# STEP_DOWN.net
KiCad netlist of a schematic drawn in Altium Designer
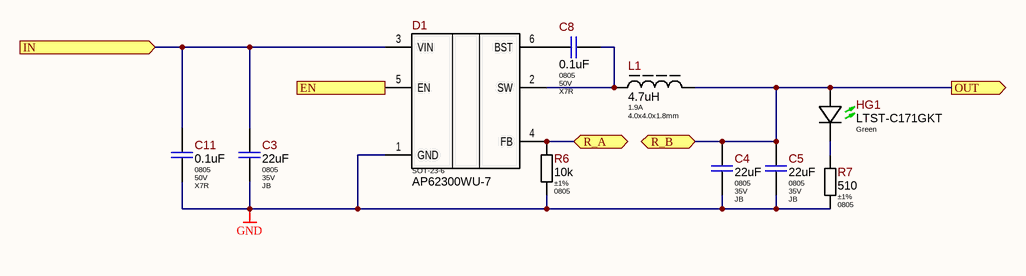
[diagram p0: STEP_DOWN.SchDoc]

(export (version "E")
  (design (tool "Eeschema 10.0.6"))
  (components
    (comp (ref "C3")
      (value "22uF")
      (footprint "CAP-0805(2012)X125T20")
      (description "22uF 35V JB ±20% 0805 Ceramic Capacitor RoHS")
      (fields
        (field (name "PACKAGE") "0805")
        (field (name "VOLTAGE") "35V")
        (field (name "DIELECTRIC TYPE") "JB")
        (field (name "PART NUMBER") "C2012JB1V226M125AC")
        (field (name "MANUFACTURER") "TDK Corporation")
      )
      (libsource (lib "capacitors") (part "C2012JB1V226M125AC"))
    )
    (comp (ref "C4")
      (value "22uF")
      (footprint "CAP-0805(2012)X125T20")
      (description "22uF 35V JB ±20% 0805 Ceramic Capacitor RoHS")
      (fields
        (field (name "PACKAGE") "0805")
        (field (name "VOLTAGE") "35V")
        (field (name "DIELECTRIC TYPE") "JB")
        (field (name "PART NUMBER") "C2012JB1V226M125AC")
        (field (name "MANUFACTURER") "TDK Corporation")
      )
      (libsource (lib "capacitors") (part "C2012JB1V226M125AC"))
    )
    (comp (ref "C5")
      (value "22uF")
      (footprint "CAP-0805(2012)X125T20")
      (description "22uF 35V JB ±20% 0805 Ceramic Capacitor RoHS")
      (fields
        (field (name "PACKAGE") "0805")
        (field (name "VOLTAGE") "35V")
        (field (name "DIELECTRIC TYPE") "JB")
        (field (name "PART NUMBER") "C2012JB1V226M125AC")
        (field (name "MANUFACTURER") "TDK Corporation")
      )
      (libsource (lib "capacitors") (part "C2012JB1V226M125AC"))
    )
    (comp (ref "C8")
      (value "0.1uF")
      (footprint "CAP-0805(2012)X85T10")
      (description "100nF 50V X7R ±10% 0805 Ceramic Capacitor RoHS")
      (fields
        (field (name "PACKAGE") "0805")
        (field (name "VOLTAGE") "50V")
        (field (name "DIELECTRIC TYPE") "X7R")
        (field (name "PART NUMBER") "CL21B104KBCNNNC")
        (field (name "MANUFACTURER") "Samsung Electro-Mechanics")
      )
      (libsource (lib "capacitors") (part "CL21B104KBCNNNC"))
    )
    (comp (ref "C11")
      (value "0.1uF")
      (footprint "CAP-0805(2012)X85T10")
      (description "100nF 50V X7R ±10% 0805 Ceramic Capacitor RoHS")
      (fields
        (field (name "PACKAGE") "0805")
        (field (name "VOLTAGE") "50V")
        (field (name "DIELECTRIC TYPE") "X7R")
        (field (name "PART NUMBER") "CL21B104KBCNNNC")
        (field (name "MANUFACTURER") "Samsung Electro-Mechanics")
      )
      (libsource (lib "capacitors") (part "CL21B104KBCNNNC"))
    )
    (comp (ref "D1")
      (value "AP62300WU-7")
      (footprint "SOT-23-6")
      (description "4.35V to 18V, 2A, High Efficiency Synchronous Step Down Converter, 500kHz, SOT-23-6")
      (fields
        (field (name "MANUFACTURER") "Diodes Incorporated")
        (field (name "PACKAGE") "SOT-23-6")
        (field (name "PART NUMBER") "AP62300WU-7")
      )
      (libsource (lib "CAMLIB") (part "AP62300WU-7"))
    )
    (comp (ref "HG1")
      (value "LTST-C171GKT")
      (footprint "LTST-C171GKT")
      (description "Low Power LED, Green 565nm, Clear, SMD 0805, Vf 2.1V - 2.6V, 5 ~ 12mcd @ 20 mA, 130°")
      (fields
        (field (name "PART NUMBER") "LTST-C171GKT")
        (field (name "COLOR") "Green")
        (field (name "MANUFACTURER") "Lite-On Optoelectronics")
      )
      (libsource (lib "opto") (part "LTST-C171GKT"))
    )
    (comp (ref "L1")
      (value "4.7uH")
      (footprint "SRN4018-Series_1.8mm")
      (description "4.7uH Semi-Shielded Wirewound Inductor 1.9A 84mOhm Max")
      (fields
        (field (name "CURRENT") "1.9A")
        (field (name "PACKAGE") "4.0x4.0x1.8mm")
        (field (name "PART NUMBER") "SRN4018-4R7M")
        (field (name "TOLERANCE") "±20%")
      )
      (libsource (lib "inductors") (part "SRN4018-4R7M"))
    )
    (comp (ref "R6")
      (value "10k")
      (footprint "R_ANY_CHIP_0805_MED")
      (description "10 kOhms ±1%, 1/8W 0805 Thick Film Resistor")
      (fields
        (field (name "TOLERANCE") "±1%")
        (field (name "PACKAGE") "0805")
        (field (name "PART NUMBER") "RC0805FR-0710K2L")
        (field (name "MANUFACTURER") "Yageo")
      )
      (libsource (lib "resistors") (part "RC0805FR-0710K2L"))
    )
    (comp (ref "R7")
      (value "510")
      (footprint "R_ANY_CHIP_0805_MED")
      (description "510 Ohms ±1%, 1/2W 0805 High Power Thick Film Resistor")
      (fields
        (field (name "TOLERANCE") "±1%")
        (field (name "PACKAGE") "0805")
        (field (name "PART NUMBER") "ERJ-P06F5100V")
        (field (name "MANUFACTURER") "Panasonic")
      )
      (libsource (lib "resistors") (part "ERJ-P06F5100V"))
    )
  )
  (nets
    (net (code "1") (name "/EN") (class "Default")
      (node (ref "D1") (pin "5") (pinfunction "EN_5") (pintype "passive"))
    )
    (net (code "2") (name "/IN") (class "Default")
      (node (ref "C11") (pin "1") (pinfunction "1_1") (pintype "passive"))
      (node (ref "C3") (pin "1") (pinfunction "1_1") (pintype "passive"))
      (node (ref "D1") (pin "3") (pinfunction "VIN_3") (pintype "passive"))
    )
    (net (code "3") (name "/OUT") (class "Default")
      (node (ref "C4") (pin "1") (pinfunction "1_1") (pintype "passive"))
      (node (ref "C5") (pin "1") (pinfunction "1_1") (pintype "passive"))
      (node (ref "HG1") (pin "AN") (pinfunction "Anode_AN") (pintype "passive"))
      (node (ref "L1") (pin "2") (pintype "passive"))
    )
    (net (code "4") (name "/R_A") (class "Default")
      (node (ref "D1") (pin "4") (pinfunction "FB_4") (pintype "passive"))
      (node (ref "R6") (pin "1") (pintype "passive"))
    )
    (net (code "5") (name "GND") (class "Default")
      (node (ref "C11") (pin "2") (pinfunction "2_2") (pintype "passive"))
      (node (ref "C3") (pin "2") (pinfunction "2_2") (pintype "passive"))
      (node (ref "C4") (pin "2") (pinfunction "2_2") (pintype "passive"))
      (node (ref "C5") (pin "2") (pinfunction "2_2") (pintype "passive"))
      (node (ref "D1") (pin "1") (pinfunction "GND_1") (pintype "passive"))
      (node (ref "R6") (pin "2") (pintype "passive"))
      (node (ref "R7") (pin "2") (pintype "passive"))
    )
    (net (code "6") (name "Net-(D1-BST)") (class "Default")
      (node (ref "C8") (pin "1") (pinfunction "1_1") (pintype "passive"))
      (node (ref "D1") (pin "6") (pinfunction "BST_6") (pintype "passive"))
    )
    (net (code "7") (name "Net-(D1-SW)") (class "Default")
      (node (ref "C8") (pin "2") (pinfunction "2_2") (pintype "passive"))
      (node (ref "D1") (pin "2") (pinfunction "SW_2") (pintype "passive"))
      (node (ref "L1") (pin "1") (pintype "passive"))
    )
    (net (code "8") (name "Net-(HG1-Cathode)") (class "Default")
      (node (ref "HG1") (pin "CA") (pinfunction "Cathode_CA") (pintype "passive"))
      (node (ref "R7") (pin "1") (pintype "passive"))
    )
  )
)
